# Modem.net
KiCad netlist of a schematic drawn in EAGLE
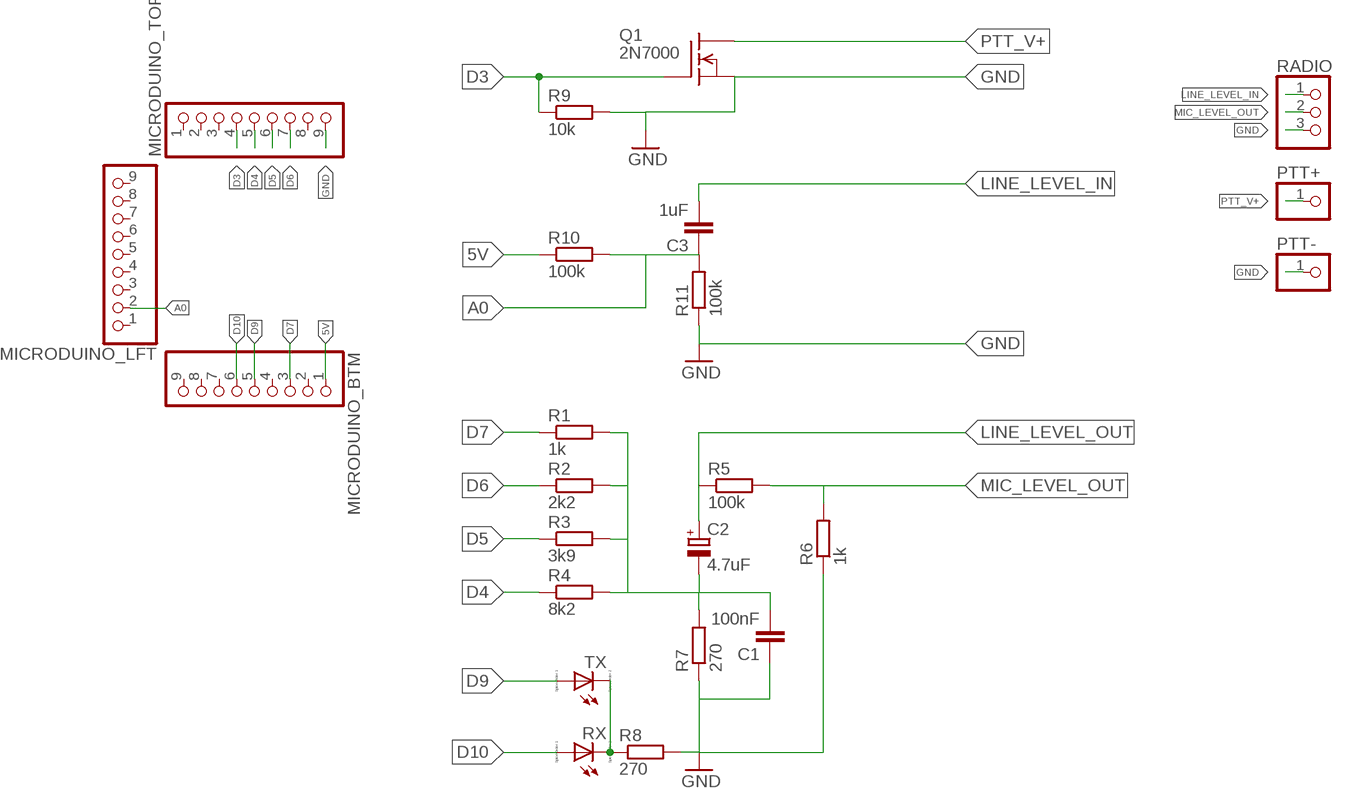
[diagram p0: schematic, sheet 1]

(export (version "E")
  (design (tool "Eeschema 10.0.6"))
  (components
    (comp (ref "C1")
      (value "100nF")
      (footprint "eagle-import:C2.5-2")
      (libsource (lib "eagle-import") (part "C2.5/2"))
    )
    (comp (ref "C2")
      (value "4.7uF")
      (footprint "eagle-import:E2,5-4R")
      (libsource (lib "eagle-import") (part "CPOL-EUE2.5-5V"))
    )
    (comp (ref "C3")
      (value "1uF")
      (footprint "eagle-import:C2.5-2")
      (libsource (lib "eagle-import") (part "C2.5/2"))
    )
    (comp (ref "MICRODUINO_BTM")
      (value "PINHD-1X9")
      (footprint "eagle-import:1X09-BIG")
      (libsource (lib "eagle-import") (part "PINHD-1X9"))
    )
    (comp (ref "MICRODUINO_LFT")
      (value "PINHD-1X9")
      (footprint "eagle-import:1X09-BIG")
      (libsource (lib "eagle-import") (part "PINHD-1X9"))
    )
    (comp (ref "MICRODUINO_TOP")
      (value "PINHD-1X9")
      (footprint "eagle-import:1X09-BIG")
      (libsource (lib "eagle-import") (part "PINHD-1X9"))
    )
    (comp (ref "PTT+")
      (value "PINHD-1X1")
      (footprint "eagle-import:1X01")
      (libsource (lib "eagle-import") (part "PINHD-1X1"))
    )
    (comp (ref "PTT-")
      (value "PINHD-1X1")
      (footprint "eagle-import:1X01")
      (libsource (lib "eagle-import") (part "PINHD-1X1"))
    )
    (comp (ref "Q1")
      (value "2N7000")
      (footprint "eagle-import:TO92")
      (libsource (lib "eagle-import") (part "BSS295"))
    )
    (comp (ref "R1")
      (value "1k")
      (footprint "eagle-import:0204V")
      (libsource (lib "eagle-import") (part "resistor_R-EU_0204/2V"))
    )
    (comp (ref "R2")
      (value "2k2")
      (footprint "eagle-import:0204V")
      (libsource (lib "eagle-import") (part "resistor_R-EU_0204/2V"))
    )
    (comp (ref "R3")
      (value "3k9")
      (footprint "eagle-import:0204V")
      (libsource (lib "eagle-import") (part "resistor_R-EU_0204/2V"))
    )
    (comp (ref "R4")
      (value "8k2")
      (footprint "eagle-import:0204V")
      (libsource (lib "eagle-import") (part "resistor_R-EU_0204/2V"))
    )
    (comp (ref "R5")
      (value "100k")
      (footprint "eagle-import:0204V")
      (libsource (lib "eagle-import") (part "resistor_R-EU_0204/2V"))
    )
    (comp (ref "R6")
      (value "1k")
      (footprint "eagle-import:0204V")
      (libsource (lib "eagle-import") (part "resistor_R-EU_0204/2V"))
    )
    (comp (ref "R7")
      (value "270")
      (footprint "eagle-import:0204V")
      (libsource (lib "eagle-import") (part "resistor_R-EU_0204/2V"))
    )
    (comp (ref "R8")
      (value "270")
      (footprint "eagle-import:0204V")
      (libsource (lib "eagle-import") (part "resistor_R-EU_0204/2V"))
    )
    (comp (ref "R9")
      (value "10k")
      (footprint "eagle-import:0204V")
      (libsource (lib "eagle-import") (part "R-EU_0204/2V"))
    )
    (comp (ref "R10")
      (value "100k")
      (footprint "eagle-import:0204V")
      (libsource (lib "eagle-import") (part "R-EU_0204/2V"))
    )
    (comp (ref "R11")
      (value "100k")
      (footprint "eagle-import:0204V")
      (libsource (lib "eagle-import") (part "R-EU_0204/2V"))
    )
    (comp (ref "RADIO")
      (value "PINHD-1X3")
      (footprint "eagle-import:1X03")
      (libsource (lib "eagle-import") (part "PINHD-1X3"))
    )
    (comp (ref "RX")
      (value "LED_ELD260")
      (footprint "eagle-import:LED_LD260")
      (libsource (lib "eagle-import") (part "LED_ELD260"))
    )
    (comp (ref "TX")
      (value "LED_ELD260")
      (footprint "eagle-import:LED_LD260")
      (libsource (lib "eagle-import") (part "LED_ELD260"))
    )
  )
  (nets
    (net (code "1") (name "5V") (class "Default")
      (node (ref "MICRODUINO_BTM") (pin "1") (pinfunction "1_1") (pintype "passive"))
      (node (ref "R10") (pin "1") (pinfunction "1_1") (pintype "passive"))
    )
    (net (code "2") (name "A0") (class "Default")
      (node (ref "C3") (pin "1") (pinfunction "1_1") (pintype "passive"))
      (node (ref "MICRODUINO_LFT") (pin "2") (pinfunction "2_2") (pintype "passive"))
      (node (ref "R10") (pin "2") (pinfunction "2_2") (pintype "passive"))
      (node (ref "R11") (pin "2") (pinfunction "2_2") (pintype "passive"))
    )
    (net (code "3") (name "D3") (class "Default")
      (node (ref "MICRODUINO_TOP") (pin "4") (pinfunction "4_4") (pintype "passive"))
      (node (ref "Q1") (pin "1") (pinfunction "G_1") (pintype "passive"))
      (node (ref "R9") (pin "1") (pinfunction "1_1") (pintype "passive"))
    )
    (net (code "4") (name "D4") (class "Default")
      (node (ref "MICRODUINO_TOP") (pin "5") (pinfunction "5_5") (pintype "passive"))
      (node (ref "R4") (pin "1") (pinfunction "1_1") (pintype "passive"))
    )
    (net (code "5") (name "D5") (class "Default")
      (node (ref "MICRODUINO_TOP") (pin "6") (pinfunction "6_6") (pintype "passive"))
      (node (ref "R3") (pin "1") (pinfunction "1_1") (pintype "passive"))
    )
    (net (code "6") (name "D6") (class "Default")
      (node (ref "MICRODUINO_TOP") (pin "7") (pinfunction "7_7") (pintype "passive"))
      (node (ref "R2") (pin "1") (pinfunction "1_1") (pintype "passive"))
    )
    (net (code "7") (name "D7") (class "Default")
      (node (ref "MICRODUINO_BTM") (pin "3") (pinfunction "3_3") (pintype "passive"))
      (node (ref "R1") (pin "1") (pinfunction "1_1") (pintype "passive"))
    )
    (net (code "8") (name "D9") (class "Default")
      (node (ref "MICRODUINO_BTM") (pin "5") (pinfunction "5_5") (pintype "passive"))
      (node (ref "TX") (pin "A") (pinfunction "A_A") (pintype "passive"))
    )
    (net (code "9") (name "D10") (class "Default")
      (node (ref "MICRODUINO_BTM") (pin "6") (pinfunction "6_6") (pintype "passive"))
      (node (ref "RX") (pin "A") (pinfunction "A_A") (pintype "passive"))
    )
    (net (code "10") (name "GND") (class "Default")
      (node (ref "C1") (pin "1") (pinfunction "1_1") (pintype "passive"))
      (node (ref "MICRODUINO_TOP") (pin "9") (pinfunction "9_9") (pintype "passive"))
      (node (ref "PTT-") (pin "1") (pinfunction "1_1") (pintype "passive"))
      (node (ref "Q1") (pin "3") (pinfunction "S_3") (pintype "passive"))
      (node (ref "R11") (pin "1") (pinfunction "1_1") (pintype "passive"))
      (node (ref "R6") (pin "1") (pinfunction "1_1") (pintype "passive"))
      (node (ref "R7") (pin "1") (pinfunction "1_1") (pintype "passive"))
      (node (ref "R8") (pin "2") (pinfunction "2_2") (pintype "passive"))
      (node (ref "R9") (pin "2") (pinfunction "2_2") (pintype "passive"))
      (node (ref "RADIO") (pin "3") (pinfunction "3_3") (pintype "passive"))
    )
    (net (code "11") (name "LINE_LEVEL_IN") (class "Default")
      (node (ref "C3") (pin "2") (pinfunction "2_2") (pintype "passive"))
      (node (ref "RADIO") (pin "1") (pinfunction "1_1") (pintype "passive"))
    )
    (net (code "12") (name "LINE_LEVEL_OUT") (class "Default")
      (node (ref "C2") (pin "+") (pinfunction "+_+") (pintype "passive"))
      (node (ref "R5") (pin "1") (pinfunction "1_1") (pintype "passive"))
    )
    (net (code "13") (name "MIC_LEVEL_OUT") (class "Default")
      (node (ref "R5") (pin "2") (pinfunction "2_2") (pintype "passive"))
      (node (ref "R6") (pin "2") (pinfunction "2_2") (pintype "passive"))
      (node (ref "RADIO") (pin "2") (pinfunction "2_2") (pintype "passive"))
    )
    (net (code "14") (name "Net-(C1-Pad2)") (class "Default")
      (node (ref "C1") (pin "2") (pinfunction "2_2") (pintype "passive"))
      (node (ref "C2") (pin "-") (pinfunction "-_-") (pintype "passive"))
      (node (ref "R1") (pin "2") (pinfunction "2_2") (pintype "passive"))
      (node (ref "R2") (pin "2") (pinfunction "2_2") (pintype "passive"))
      (node (ref "R3") (pin "2") (pinfunction "2_2") (pintype "passive"))
      (node (ref "R4") (pin "2") (pinfunction "2_2") (pintype "passive"))
      (node (ref "R7") (pin "2") (pinfunction "2_2") (pintype "passive"))
    )
    (net (code "15") (name "Net-(RX-C)") (class "Default")
      (node (ref "R8") (pin "1") (pinfunction "1_1") (pintype "passive"))
      (node (ref "RX") (pin "K") (pinfunction "C_K") (pintype "passive"))
      (node (ref "TX") (pin "K") (pinfunction "C_K") (pintype "passive"))
    )
    (net (code "16") (name "PTT_V+") (class "Default")
      (node (ref "PTT+") (pin "1") (pinfunction "1_1") (pintype "passive"))
      (node (ref "Q1") (pin "2") (pinfunction "D_2") (pintype "passive"))
    )
    (net (code "17") (name "unconnected-(MICRODUINO_BTM-Pad2)") (class "Default")
      (node (ref "MICRODUINO_BTM") (pin "2") (pinfunction "2_2") (pintype "passive"))
    )
    (net (code "18") (name "unconnected-(MICRODUINO_BTM-Pad4)") (class "Default")
      (node (ref "MICRODUINO_BTM") (pin "4") (pinfunction "4_4") (pintype "passive"))
    )
    (net (code "19") (name "unconnected-(MICRODUINO_BTM-Pad7)") (class "Default")
      (node (ref "MICRODUINO_BTM") (pin "7") (pinfunction "7_7") (pintype "passive"))
    )
    (net (code "20") (name "unconnected-(MICRODUINO_BTM-Pad8)") (class "Default")
      (node (ref "MICRODUINO_BTM") (pin "8") (pinfunction "8_8") (pintype "passive"))
    )
    (net (code "21") (name "unconnected-(MICRODUINO_BTM-Pad9)") (class "Default")
      (node (ref "MICRODUINO_BTM") (pin "9") (pinfunction "9_9") (pintype "passive"))
    )
    (net (code "22") (name "unconnected-(MICRODUINO_LFT-Pad1)") (class "Default")
      (node (ref "MICRODUINO_LFT") (pin "1") (pinfunction "1_1") (pintype "passive"))
    )
    (net (code "23") (name "unconnected-(MICRODUINO_LFT-Pad3)") (class "Default")
      (node (ref "MICRODUINO_LFT") (pin "3") (pinfunction "3_3") (pintype "passive"))
    )
    (net (code "24") (name "unconnected-(MICRODUINO_LFT-Pad4)") (class "Default")
      (node (ref "MICRODUINO_LFT") (pin "4") (pinfunction "4_4") (pintype "passive"))
    )
    (net (code "25") (name "unconnected-(MICRODUINO_LFT-Pad5)") (class "Default")
      (node (ref "MICRODUINO_LFT") (pin "5") (pinfunction "5_5") (pintype "passive"))
    )
    (net (code "26") (name "unconnected-(MICRODUINO_LFT-Pad6)") (class "Default")
      (node (ref "MICRODUINO_LFT") (pin "6") (pinfunction "6_6") (pintype "passive"))
    )
    (net (code "27") (name "unconnected-(MICRODUINO_LFT-Pad7)") (class "Default")
      (node (ref "MICRODUINO_LFT") (pin "7") (pinfunction "7_7") (pintype "passive"))
    )
    (net (code "28") (name "unconnected-(MICRODUINO_LFT-Pad8)") (class "Default")
      (node (ref "MICRODUINO_LFT") (pin "8") (pinfunction "8_8") (pintype "passive"))
    )
    (net (code "29") (name "unconnected-(MICRODUINO_LFT-Pad9)") (class "Default")
      (node (ref "MICRODUINO_LFT") (pin "9") (pinfunction "9_9") (pintype "passive"))
    )
    (net (code "30") (name "unconnected-(MICRODUINO_TOP-Pad1)") (class "Default")
      (node (ref "MICRODUINO_TOP") (pin "1") (pinfunction "1_1") (pintype "passive"))
    )
    (net (code "31") (name "unconnected-(MICRODUINO_TOP-Pad2)") (class "Default")
      (node (ref "MICRODUINO_TOP") (pin "2") (pinfunction "2_2") (pintype "passive"))
    )
    (net (code "32") (name "unconnected-(MICRODUINO_TOP-Pad3)") (class "Default")
      (node (ref "MICRODUINO_TOP") (pin "3") (pinfunction "3_3") (pintype "passive"))
    )
    (net (code "33") (name "unconnected-(MICRODUINO_TOP-Pad8)") (class "Default")
      (node (ref "MICRODUINO_TOP") (pin "8") (pinfunction "8_8") (pintype "passive"))
    )
  )
)
